# Placa_processamento_modelo_A.net
KiCad netlist of a schematic drawn in EAGLE
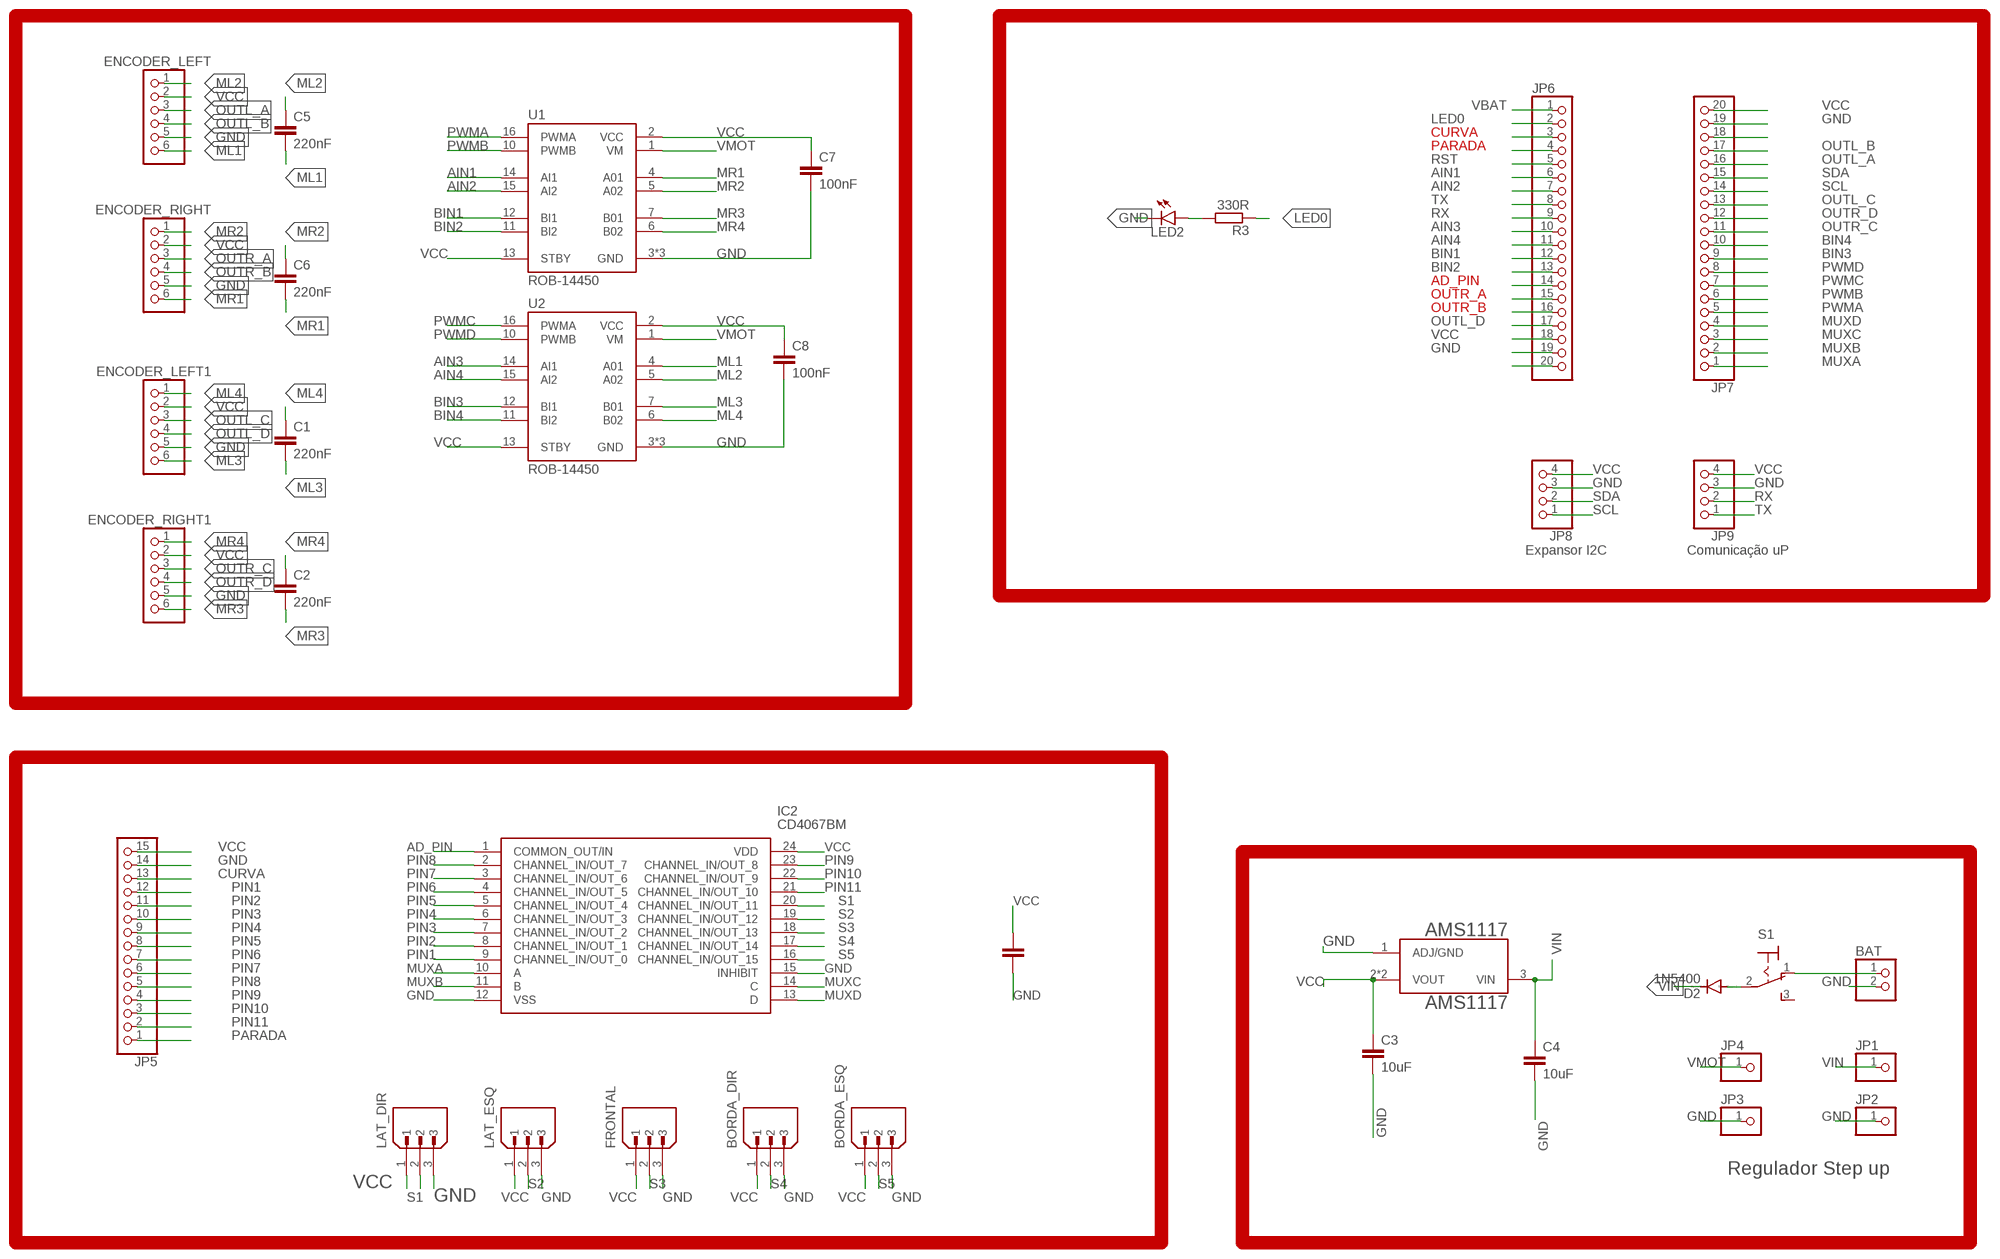
[diagram p0: schematic, sheet 1]

(export (version "E")
  (design (tool "Eeschema 10.0.6"))
  (components
    (comp (ref "AMS1117")
      (value "AMS1117")
      (footprint "eagle-import:SOT229P700X180-4N")
      (fields (field (name "MF") "Advanced Monolithic Systems"))
      (libsource (lib "eagle-import") (part "AMS1117"))
    )
    (comp (ref "BAT")
      (value "PINHD-1X2")
      (footprint "eagle-import:1X02")
      (libsource (lib "eagle-import") (part "PINHD-1X2"))
    )
    (comp (ref "BORDA_DIR")
      (value "B3B-XH-A(LF)(SN)")
      (footprint "eagle-import:JST_B3B-XH-A(LF)(SN)")
      (fields (field (name "MF") "JST Sales"))
      (libsource (lib "eagle-import") (part "B3B-XH-A(LF)(SN)"))
    )
    (comp (ref "BORDA_ESQ")
      (value "B3B-XH-A(LF)(SN)")
      (footprint "eagle-import:JST_B3B-XH-A(LF)(SN)")
      (fields (field (name "MF") "JST Sales"))
      (libsource (lib "eagle-import") (part "B3B-XH-A(LF)(SN)"))
    )
    (comp (ref "C1")
      (value "220nF")
      (footprint "eagle-import:C0805")
      (libsource (lib "eagle-import") (part "C-EUC0805"))
    )
    (comp (ref "C2")
      (value "220nF")
      (footprint "eagle-import:C0805")
      (libsource (lib "eagle-import") (part "C-EUC0805"))
    )
    (comp (ref "C3")
      (value "10uF")
      (footprint "eagle-import:C0805")
      (libsource (lib "eagle-import") (part "C-EUC0805"))
    )
    (comp (ref "C4")
      (value "10uF")
      (footprint "eagle-import:C0805")
      (libsource (lib "eagle-import") (part "C-EUC0805"))
    )
    (comp (ref "C5")
      (value "220nF")
      (footprint "eagle-import:C0805")
      (libsource (lib "eagle-import") (part "C-EUC0805"))
    )
    (comp (ref "C6")
      (value "220nF")
      (footprint "eagle-import:C0805")
      (libsource (lib "eagle-import") (part "C-EUC0805"))
    )
    (comp (ref "C7")
      (value "100nF")
      (footprint "eagle-import:C0805")
      (libsource (lib "eagle-import") (part "C-EUC0805"))
    )
    (comp (ref "C8")
      (value "100nF")
      (footprint "eagle-import:C0805")
      (libsource (lib "eagle-import") (part "C-EUC0805"))
    )
    (comp (ref "C10")
      (value "100nF")
      (footprint "eagle-import:C0805")
      (libsource (lib "eagle-import") (part "C-EUC0805"))
    )
    (comp (ref "D2")
      (value "1N5400")
      (footprint "eagle-import:DO201-15")
      (libsource (lib "eagle-import") (part "1N5400"))
    )
    (comp (ref "ENCODER_LEFT")
      (value "PINHD-1X6")
      (footprint "eagle-import:1X06")
      (libsource (lib "eagle-import") (part "PINHD-1X6"))
    )
    (comp (ref "ENCODER_LEFT1")
      (value "PINHD-1X6")
      (footprint "eagle-import:1X06")
      (libsource (lib "eagle-import") (part "PINHD-1X6"))
    )
    (comp (ref "ENCODER_RIGHT")
      (value "PINHD-1X6")
      (footprint "eagle-import:1X06")
      (libsource (lib "eagle-import") (part "PINHD-1X6"))
    )
    (comp (ref "ENCODER_RIGHT1")
      (value "PINHD-1X6")
      (footprint "eagle-import:1X06")
      (libsource (lib "eagle-import") (part "PINHD-1X6"))
    )
    (comp (ref "FRONTAL")
      (value "B3B-XH-A(LF)(SN)")
      (footprint "eagle-import:JST_B3B-XH-A(LF)(SN)")
      (fields (field (name "MF") "JST Sales"))
      (libsource (lib "eagle-import") (part "B3B-XH-A(LF)(SN)"))
    )
    (comp (ref "IC2")
      (value "CD4067BM")
      (footprint "eagle-import:SOIC127P1030X265-24N")
      (fields (field (name "MOUSER_PART_NUMBER") "595-CD4067BM"))
      (libsource (lib "eagle-import") (part "CD4067BM"))
    )
    (comp (ref "JP1")
      (value "PINHD-1X1")
      (footprint "eagle-import:1X01")
      (libsource (lib "eagle-import") (part "PINHD-1X1"))
    )
    (comp (ref "JP2")
      (value "PINHD-1X1")
      (footprint "eagle-import:1X01")
      (libsource (lib "eagle-import") (part "PINHD-1X1"))
    )
    (comp (ref "JP3")
      (value "PINHD-1X1")
      (footprint "eagle-import:1X01")
      (libsource (lib "eagle-import") (part "PINHD-1X1"))
    )
    (comp (ref "JP4")
      (value "PINHD-1X1")
      (footprint "eagle-import:1X01")
      (libsource (lib "eagle-import") (part "PINHD-1X1"))
    )
    (comp (ref "JP5")
      (value "PINHD-1X15")
      (footprint "eagle-import:1X15")
      (libsource (lib "eagle-import") (part "PINHD-1X15"))
    )
    (comp (ref "JP6")
      (value "PINHD-1X20")
      (footprint "eagle-import:1X20")
      (libsource (lib "eagle-import") (part "PINHD-1X20"))
    )
    (comp (ref "JP7")
      (value "PINHD-1X20")
      (footprint "eagle-import:1X20")
      (libsource (lib "eagle-import") (part "PINHD-1X20"))
    )
    (comp (ref "JP8")
      (value "PINHD-1X4")
      (footprint "eagle-import:1X04")
      (libsource (lib "eagle-import") (part "PINHD-1X4"))
    )
    (comp (ref "JP9")
      (value "PINHD-1X4")
      (footprint "eagle-import:1X04")
      (libsource (lib "eagle-import") (part "PINHD-1X4"))
    )
    (comp (ref "LAT_DIR")
      (value "B3B-XH-A(LF)(SN)")
      (footprint "eagle-import:JST_B3B-XH-A(LF)(SN)")
      (fields (field (name "MF") "JST Sales"))
      (libsource (lib "eagle-import") (part "B3B-XH-A(LF)(SN)"))
    )
    (comp (ref "LAT_ESQ")
      (value "B3B-XH-A(LF)(SN)")
      (footprint "eagle-import:JST_B3B-XH-A(LF)(SN)")
      (fields (field (name "MF") "JST Sales"))
      (libsource (lib "eagle-import") (part "B3B-XH-A(LF)(SN)"))
    )
    (comp (ref "LED2")
      (value "LEDCHIPLED_0805")
      (footprint "eagle-import:CHIPLED_0805")
      (libsource (lib "eagle-import") (part "LEDCHIPLED_0805"))
    )
    (comp (ref "R3")
      (value "330R")
      (footprint "eagle-import:R0805")
      (libsource (lib "eagle-import") (part "R-EU_R0805"))
    )
    (comp (ref "S1")
      (value "320-916")
      (footprint "eagle-import:320-916")
      (libsource (lib "eagle-import") (part "320-916"))
    )
    (comp (ref "U1")
      (value "ROB-14450")
      (footprint "eagle-import:MODULE_ROB-14450")
      (fields (field (name "MF") "SparkFun Electronics"))
      (libsource (lib "eagle-import") (part "ROB-14450"))
    )
    (comp (ref "U2")
      (value "ROB-14450")
      (footprint "eagle-import:MODULE_ROB-14450")
      (fields (field (name "MF") "SparkFun Electronics"))
      (libsource (lib "eagle-import") (part "ROB-14450"))
    )
  )
  (nets
    (net (code "1") (name "/AD_PIN") (class "Default")
      (node (ref "IC2") (pin "1") (pinfunction "COMMON_OUT/IN_1") (pintype "bidirectional"))
      (node (ref "JP6") (pin "14") (pinfunction "14_14") (pintype "passive"))
    )
    (net (code "2") (name "/AIN1") (class "Default")
      (node (ref "JP6") (pin "6") (pinfunction "6_6") (pintype "passive"))
      (node (ref "U1") (pin "14") (pinfunction "AI1_14") (pintype "input"))
    )
    (net (code "3") (name "/AIN2") (class "Default")
      (node (ref "JP6") (pin "7") (pinfunction "7_7") (pintype "passive"))
      (node (ref "U1") (pin "15") (pinfunction "AI2_15") (pintype "input"))
    )
    (net (code "4") (name "/AIN3") (class "Default")
      (node (ref "JP6") (pin "10") (pinfunction "10_10") (pintype "passive"))
      (node (ref "U2") (pin "14") (pinfunction "AI1_14") (pintype "input"))
    )
    (net (code "5") (name "/AIN4") (class "Default")
      (node (ref "JP6") (pin "11") (pinfunction "11_11") (pintype "passive"))
      (node (ref "U2") (pin "15") (pinfunction "AI2_15") (pintype "input"))
    )
    (net (code "6") (name "/BIN1") (class "Default")
      (node (ref "JP6") (pin "12") (pinfunction "12_12") (pintype "passive"))
      (node (ref "U1") (pin "12") (pinfunction "BI1_12") (pintype "input"))
    )
    (net (code "7") (name "/BIN2") (class "Default")
      (node (ref "JP6") (pin "13") (pinfunction "13_13") (pintype "passive"))
      (node (ref "U1") (pin "11") (pinfunction "BI2_11") (pintype "input"))
    )
    (net (code "8") (name "/BIN3") (class "Default")
      (node (ref "JP7") (pin "9") (pinfunction "9_9") (pintype "passive"))
      (node (ref "U2") (pin "12") (pinfunction "BI1_12") (pintype "input"))
    )
    (net (code "9") (name "/BIN4") (class "Default")
      (node (ref "JP7") (pin "10") (pinfunction "10_10") (pintype "passive"))
      (node (ref "U2") (pin "11") (pinfunction "BI2_11") (pintype "input"))
    )
    (net (code "10") (name "/CURVA") (class "Default")
      (node (ref "JP5") (pin "13") (pinfunction "13_13") (pintype "passive"))
      (node (ref "JP6") (pin "3") (pinfunction "3_3") (pintype "passive"))
    )
    (net (code "11") (name "/MUXA") (class "Default")
      (node (ref "IC2") (pin "10") (pinfunction "A_10") (pintype "bidirectional"))
      (node (ref "JP7") (pin "1") (pinfunction "1_1") (pintype "passive"))
    )
    (net (code "12") (name "/MUXB") (class "Default")
      (node (ref "IC2") (pin "11") (pinfunction "B_11") (pintype "bidirectional"))
      (node (ref "JP7") (pin "2") (pinfunction "2_2") (pintype "passive"))
    )
    (net (code "13") (name "/MUXC") (class "Default")
      (node (ref "IC2") (pin "14") (pinfunction "C_14") (pintype "bidirectional"))
      (node (ref "JP7") (pin "3") (pinfunction "3_3") (pintype "passive"))
    )
    (net (code "14") (name "/MUXD") (class "Default")
      (node (ref "IC2") (pin "13") (pinfunction "D_13") (pintype "bidirectional"))
      (node (ref "JP7") (pin "4") (pinfunction "4_4") (pintype "passive"))
    )
    (net (code "15") (name "/PARADA") (class "Default")
      (node (ref "JP5") (pin "1") (pinfunction "1_1") (pintype "passive"))
      (node (ref "JP6") (pin "4") (pinfunction "4_4") (pintype "passive"))
    )
    (net (code "16") (name "/PIN1") (class "Default")
      (node (ref "IC2") (pin "9") (pinfunction "CHANNEL_IN/OUT_0_9") (pintype "bidirectional"))
      (node (ref "JP5") (pin "12") (pinfunction "12_12") (pintype "passive"))
    )
    (net (code "17") (name "/PIN2") (class "Default")
      (node (ref "IC2") (pin "8") (pinfunction "CHANNEL_IN/OUT_1_8") (pintype "bidirectional"))
      (node (ref "JP5") (pin "11") (pinfunction "11_11") (pintype "passive"))
    )
    (net (code "18") (name "/PIN3") (class "Default")
      (node (ref "IC2") (pin "7") (pinfunction "CHANNEL_IN/OUT_2_7") (pintype "bidirectional"))
      (node (ref "JP5") (pin "10") (pinfunction "10_10") (pintype "passive"))
    )
    (net (code "19") (name "/PIN4") (class "Default")
      (node (ref "IC2") (pin "6") (pinfunction "CHANNEL_IN/OUT_3_6") (pintype "bidirectional"))
      (node (ref "JP5") (pin "9") (pinfunction "9_9") (pintype "passive"))
    )
    (net (code "20") (name "/PIN5") (class "Default")
      (node (ref "IC2") (pin "5") (pinfunction "CHANNEL_IN/OUT_4_5") (pintype "bidirectional"))
      (node (ref "JP5") (pin "8") (pinfunction "8_8") (pintype "passive"))
    )
    (net (code "21") (name "/PIN6") (class "Default")
      (node (ref "IC2") (pin "4") (pinfunction "CHANNEL_IN/OUT_5_4") (pintype "bidirectional"))
      (node (ref "JP5") (pin "7") (pinfunction "7_7") (pintype "passive"))
    )
    (net (code "22") (name "/PIN7") (class "Default")
      (node (ref "IC2") (pin "3") (pinfunction "CHANNEL_IN/OUT_6_3") (pintype "bidirectional"))
      (node (ref "JP5") (pin "6") (pinfunction "6_6") (pintype "passive"))
    )
    (net (code "23") (name "/PIN8") (class "Default")
      (node (ref "IC2") (pin "2") (pinfunction "CHANNEL_IN/OUT_7_2") (pintype "bidirectional"))
      (node (ref "JP5") (pin "5") (pinfunction "5_5") (pintype "passive"))
    )
    (net (code "24") (name "/PIN9") (class "Default")
      (node (ref "IC2") (pin "23") (pinfunction "CHANNEL_IN/OUT_8_23") (pintype "bidirectional"))
      (node (ref "JP5") (pin "4") (pinfunction "4_4") (pintype "passive"))
    )
    (net (code "25") (name "/PIN10") (class "Default")
      (node (ref "IC2") (pin "22") (pinfunction "CHANNEL_IN/OUT_9_22") (pintype "bidirectional"))
      (node (ref "JP5") (pin "3") (pinfunction "3_3") (pintype "passive"))
    )
    (net (code "26") (name "/PIN11") (class "Default")
      (node (ref "IC2") (pin "21") (pinfunction "CHANNEL_IN/OUT_10_21") (pintype "bidirectional"))
      (node (ref "JP5") (pin "2") (pinfunction "2_2") (pintype "passive"))
    )
    (net (code "27") (name "/PWMA") (class "Default")
      (node (ref "JP7") (pin "5") (pinfunction "5_5") (pintype "passive"))
      (node (ref "U1") (pin "16") (pinfunction "PWMA_16") (pintype "input"))
    )
    (net (code "28") (name "/PWMB") (class "Default")
      (node (ref "JP7") (pin "6") (pinfunction "6_6") (pintype "passive"))
      (node (ref "U1") (pin "10") (pinfunction "PWMB_10") (pintype "input"))
    )
    (net (code "29") (name "/PWMC") (class "Default")
      (node (ref "JP7") (pin "7") (pinfunction "7_7") (pintype "passive"))
      (node (ref "U2") (pin "16") (pinfunction "PWMA_16") (pintype "input"))
    )
    (net (code "30") (name "/PWMD") (class "Default")
      (node (ref "JP7") (pin "8") (pinfunction "8_8") (pintype "passive"))
      (node (ref "U2") (pin "10") (pinfunction "PWMB_10") (pintype "input"))
    )
    (net (code "31") (name "/RST") (class "Default")
      (node (ref "JP6") (pin "5") (pinfunction "5_5") (pintype "passive"))
    )
    (net (code "32") (name "/RX") (class "Default")
      (node (ref "JP6") (pin "9") (pinfunction "9_9") (pintype "passive"))
      (node (ref "JP9") (pin "2") (pinfunction "2_2") (pintype "passive"))
    )
    (net (code "33") (name "/S1") (class "Default")
      (node (ref "IC2") (pin "20") (pinfunction "CHANNEL_IN/OUT_11_20") (pintype "bidirectional"))
      (node (ref "LAT_DIR") (pin "2") (pinfunction "2_2") (pintype "passive"))
    )
    (net (code "34") (name "/S2") (class "Default")
      (node (ref "IC2") (pin "19") (pinfunction "CHANNEL_IN/OUT_12_19") (pintype "bidirectional"))
      (node (ref "LAT_ESQ") (pin "2") (pinfunction "2_2") (pintype "passive"))
    )
    (net (code "35") (name "/S3") (class "Default")
      (node (ref "FRONTAL") (pin "2") (pinfunction "2_2") (pintype "passive"))
      (node (ref "IC2") (pin "18") (pinfunction "CHANNEL_IN/OUT_13_18") (pintype "bidirectional"))
    )
    (net (code "36") (name "/S4") (class "Default")
      (node (ref "BORDA_DIR") (pin "2") (pinfunction "2_2") (pintype "passive"))
      (node (ref "IC2") (pin "17") (pinfunction "CHANNEL_IN/OUT_14_17") (pintype "bidirectional"))
    )
    (net (code "37") (name "/S5") (class "Default")
      (node (ref "BORDA_ESQ") (pin "2") (pinfunction "2_2") (pintype "passive"))
      (node (ref "IC2") (pin "16") (pinfunction "CHANNEL_IN/OUT_15_16") (pintype "bidirectional"))
    )
    (net (code "38") (name "/SCL") (class "Default")
      (node (ref "JP7") (pin "14") (pinfunction "14_14") (pintype "passive"))
      (node (ref "JP8") (pin "1") (pinfunction "1_1") (pintype "passive"))
    )
    (net (code "39") (name "/SDA") (class "Default")
      (node (ref "JP7") (pin "15") (pinfunction "15_15") (pintype "passive"))
      (node (ref "JP8") (pin "2") (pinfunction "2_2") (pintype "passive"))
    )
    (net (code "40") (name "/TX") (class "Default")
      (node (ref "JP6") (pin "8") (pinfunction "8_8") (pintype "passive"))
      (node (ref "JP9") (pin "1") (pinfunction "1_1") (pintype "passive"))
    )
    (net (code "41") (name "/VBAT") (class "Default")
      (node (ref "JP6") (pin "1") (pinfunction "1_1") (pintype "passive"))
    )
    (net (code "42") (name "/VMOT") (class "Default")
      (node (ref "JP4") (pin "1") (pinfunction "1_1") (pintype "passive"))
      (node (ref "U1") (pin "1") (pinfunction "VM_1") (pintype "power_in"))
      (node (ref "U2") (pin "1") (pinfunction "VM_1") (pintype "power_in"))
    )
    (net (code "43") (name "GND") (class "Default")
      (node (ref "AMS1117") (pin "1") (pinfunction "ADJ/GND_1") (pintype "power_in"))
      (node (ref "BAT") (pin "2") (pinfunction "2_2") (pintype "passive"))
      (node (ref "BORDA_DIR") (pin "3") (pinfunction "3_3") (pintype "passive"))
      (node (ref "BORDA_ESQ") (pin "3") (pinfunction "3_3") (pintype "passive"))
      (node (ref "C10") (pin "2") (pinfunction "2_2") (pintype "passive"))
      (node (ref "C3") (pin "2") (pinfunction "2_2") (pintype "passive"))
      (node (ref "C4") (pin "2") (pinfunction "2_2") (pintype "passive"))
      (node (ref "C7") (pin "2") (pinfunction "2_2") (pintype "passive"))
      (node (ref "C8") (pin "2") (pinfunction "2_2") (pintype "passive"))
      (node (ref "ENCODER_LEFT") (pin "5") (pinfunction "5_5") (pintype "passive"))
      (node (ref "ENCODER_LEFT1") (pin "5") (pinfunction "5_5") (pintype "passive"))
      (node (ref "ENCODER_RIGHT") (pin "5") (pinfunction "5_5") (pintype "passive"))
      (node (ref "ENCODER_RIGHT1") (pin "5") (pinfunction "5_5") (pintype "passive"))
      (node (ref "FRONTAL") (pin "3") (pinfunction "3_3") (pintype "passive"))
      (node (ref "IC2") (pin "12") (pinfunction "VSS_12") (pintype "bidirectional"))
      (node (ref "IC2") (pin "15") (pinfunction "INHIBIT_15") (pintype "bidirectional"))
      (node (ref "JP2") (pin "1") (pinfunction "1_1") (pintype "passive"))
      (node (ref "JP3") (pin "1") (pinfunction "1_1") (pintype "passive"))
      (node (ref "JP5") (pin "14") (pinfunction "14_14") (pintype "passive"))
      (node (ref "JP6") (pin "19") (pinfunction "19_19") (pintype "passive"))
      (node (ref "JP7") (pin "19") (pinfunction "19_19") (pintype "passive"))
      (node (ref "JP8") (pin "3") (pinfunction "3_3") (pintype "passive"))
      (node (ref "JP9") (pin "3") (pinfunction "3_3") (pintype "passive"))
      (node (ref "LAT_DIR") (pin "3") (pinfunction "3_3") (pintype "passive"))
      (node (ref "LAT_ESQ") (pin "3") (pinfunction "3_3") (pintype "passive"))
      (node (ref "LED2") (pin "C") (pinfunction "C_C") (pintype "passive"))
      (node (ref "U1") (pin "3") (pinfunction "GND_3") (pintype "power_in"))
      (node (ref "U1") (pin "8") (pinfunction "GND_8") (pintype "power_in"))
      (node (ref "U1") (pin "9") (pinfunction "GND_9") (pintype "power_in"))
      (node (ref "U2") (pin "3") (pinfunction "GND_3") (pintype "power_in"))
      (node (ref "U2") (pin "8") (pinfunction "GND_8") (pintype "power_in"))
      (node (ref "U2") (pin "9") (pinfunction "GND_9") (pintype "power_in"))
    )
    (net (code "44") (name "LED0") (class "Default")
      (node (ref "JP6") (pin "2") (pinfunction "2_2") (pintype "passive"))
      (node (ref "R3") (pin "1") (pinfunction "1_1") (pintype "passive"))
    )
    (net (code "45") (name "ML1") (class "Default")
      (node (ref "C5") (pin "2") (pinfunction "2_2") (pintype "passive"))
      (node (ref "ENCODER_LEFT") (pin "6") (pinfunction "6_6") (pintype "passive"))
      (node (ref "U2") (pin "4") (pinfunction "A01_4") (pintype "output"))
    )
    (net (code "46") (name "ML2") (class "Default")
      (node (ref "C5") (pin "1") (pinfunction "1_1") (pintype "passive"))
      (node (ref "ENCODER_LEFT") (pin "1") (pinfunction "1_1") (pintype "passive"))
      (node (ref "U2") (pin "5") (pinfunction "A02_5") (pintype "output"))
    )
    (net (code "47") (name "ML3") (class "Default")
      (node (ref "C1") (pin "2") (pinfunction "2_2") (pintype "passive"))
      (node (ref "ENCODER_LEFT1") (pin "6") (pinfunction "6_6") (pintype "passive"))
      (node (ref "U2") (pin "7") (pinfunction "B01_7") (pintype "output"))
    )
    (net (code "48") (name "ML4") (class "Default")
      (node (ref "C1") (pin "1") (pinfunction "1_1") (pintype "passive"))
      (node (ref "ENCODER_LEFT1") (pin "1") (pinfunction "1_1") (pintype "passive"))
      (node (ref "U2") (pin "6") (pinfunction "B02_6") (pintype "output"))
    )
    (net (code "49") (name "MR1") (class "Default")
      (node (ref "C6") (pin "2") (pinfunction "2_2") (pintype "passive"))
      (node (ref "ENCODER_RIGHT") (pin "6") (pinfunction "6_6") (pintype "passive"))
      (node (ref "U1") (pin "4") (pinfunction "A01_4") (pintype "output"))
    )
    (net (code "50") (name "MR2") (class "Default")
      (node (ref "C6") (pin "1") (pinfunction "1_1") (pintype "passive"))
      (node (ref "ENCODER_RIGHT") (pin "1") (pinfunction "1_1") (pintype "passive"))
      (node (ref "U1") (pin "5") (pinfunction "A02_5") (pintype "output"))
    )
    (net (code "51") (name "MR3") (class "Default")
      (node (ref "C2") (pin "2") (pinfunction "2_2") (pintype "passive"))
      (node (ref "ENCODER_RIGHT1") (pin "6") (pinfunction "6_6") (pintype "passive"))
      (node (ref "U1") (pin "7") (pinfunction "B01_7") (pintype "output"))
    )
    (net (code "52") (name "MR4") (class "Default")
      (node (ref "C2") (pin "1") (pinfunction "1_1") (pintype "passive"))
      (node (ref "ENCODER_RIGHT1") (pin "1") (pinfunction "1_1") (pintype "passive"))
      (node (ref "U1") (pin "6") (pinfunction "B02_6") (pintype "output"))
    )
    (net (code "53") (name "Net-(LED2-PadA)") (class "Default")
      (node (ref "LED2") (pin "A") (pinfunction "A_A") (pintype "passive"))
      (node (ref "R3") (pin "2") (pinfunction "2_2") (pintype "passive"))
    )
    (net (code "54") (name "Net-(S1-O)") (class "Default")
      (node (ref "BAT") (pin "1") (pinfunction "1_1") (pintype "passive"))
      (node (ref "S1") (pin "1") (pinfunction "O_1") (pintype "passive"))
    )
    (net (code "55") (name "Net-(S1-P)") (class "Default")
      (node (ref "D2") (pin "A") (pinfunction "A_A") (pintype "passive"))
      (node (ref "S1") (pin "2") (pinfunction "P_2") (pintype "passive"))
    )
    (net (code "56") (name "OUTL_A") (class "Default")
      (node (ref "ENCODER_LEFT") (pin "3") (pinfunction "3_3") (pintype "passive"))
      (node (ref "JP7") (pin "16") (pinfunction "16_16") (pintype "passive"))
    )
    (net (code "57") (name "OUTL_B") (class "Default")
      (node (ref "ENCODER_LEFT") (pin "4") (pinfunction "4_4") (pintype "passive"))
      (node (ref "JP7") (pin "17") (pinfunction "17_17") (pintype "passive"))
    )
    (net (code "58") (name "OUTL_C") (class "Default")
      (node (ref "ENCODER_LEFT1") (pin "3") (pinfunction "3_3") (pintype "passive"))
      (node (ref "JP7") (pin "13") (pinfunction "13_13") (pintype "passive"))
    )
    (net (code "59") (name "OUTL_D") (class "Default")
      (node (ref "ENCODER_LEFT1") (pin "4") (pinfunction "4_4") (pintype "passive"))
      (node (ref "JP6") (pin "17") (pinfunction "17_17") (pintype "passive"))
    )
    (net (code "60") (name "OUTR_A") (class "Default")
      (node (ref "ENCODER_RIGHT") (pin "3") (pinfunction "3_3") (pintype "passive"))
      (node (ref "JP6") (pin "15") (pinfunction "15_15") (pintype "passive"))
    )
    (net (code "61") (name "OUTR_B") (class "Default")
      (node (ref "ENCODER_RIGHT") (pin "4") (pinfunction "4_4") (pintype "passive"))
      (node (ref "JP6") (pin "16") (pinfunction "16_16") (pintype "passive"))
    )
    (net (code "62") (name "OUTR_C") (class "Default")
      (node (ref "ENCODER_RIGHT1") (pin "3") (pinfunction "3_3") (pintype "passive"))
      (node (ref "JP7") (pin "11") (pinfunction "11_11") (pintype "passive"))
    )
    (net (code "63") (name "OUTR_D") (class "Default")
      (node (ref "ENCODER_RIGHT1") (pin "4") (pinfunction "4_4") (pintype "passive"))
      (node (ref "JP7") (pin "12") (pinfunction "12_12") (pintype "passive"))
    )
    (net (code "64") (name "VCC") (class "Default")
      (node (ref "AMS1117") (pin "2") (pinfunction "VOUT_2") (pintype "output"))
      (node (ref "AMS1117") (pin "4") (pinfunction "VOUT_4") (pintype "output"))
      (node (ref "BORDA_DIR") (pin "1") (pinfunction "1_1") (pintype "passive"))
      (node (ref "BORDA_ESQ") (pin "1") (pinfunction "1_1") (pintype "passive"))
      (node (ref "C10") (pin "1") (pinfunction "1_1") (pintype "passive"))
      (node (ref "C3") (pin "1") (pinfunction "1_1") (pintype "passive"))
      (node (ref "C7") (pin "1") (pinfunction "1_1") (pintype "passive"))
      (node (ref "C8") (pin "1") (pinfunction "1_1") (pintype "passive"))
      (node (ref "ENCODER_LEFT") (pin "2") (pinfunction "2_2") (pintype "passive"))
      (node (ref "ENCODER_LEFT1") (pin "2") (pinfunction "2_2") (pintype "passive"))
      (node (ref "ENCODER_RIGHT") (pin "2") (pinfunction "2_2") (pintype "passive"))
      (node (ref "ENCODER_RIGHT1") (pin "2") (pinfunction "2_2") (pintype "passive"))
      (node (ref "FRONTAL") (pin "1") (pinfunction "1_1") (pintype "passive"))
      (node (ref "IC2") (pin "24") (pinfunction "VDD_24") (pintype "bidirectional"))
      (node (ref "JP5") (pin "15") (pinfunction "15_15") (pintype "passive"))
      (node (ref "JP6") (pin "18") (pinfunction "18_18") (pintype "passive"))
      (node (ref "JP7") (pin "20") (pinfunction "20_20") (pintype "passive"))
      (node (ref "JP8") (pin "4") (pinfunction "4_4") (pintype "passive"))
      (node (ref "JP9") (pin "4") (pinfunction "4_4") (pintype "passive"))
      (node (ref "LAT_DIR") (pin "1") (pinfunction "1_1") (pintype "passive"))
      (node (ref "LAT_ESQ") (pin "1") (pinfunction "1_1") (pintype "passive"))
      (node (ref "U1") (pin "13") (pinfunction "STBY_13") (pintype "input"))
      (node (ref "U1") (pin "2") (pinfunction "VCC_2") (pintype "power_in"))
      (node (ref "U2") (pin "13") (pinfunction "STBY_13") (pintype "input"))
      (node (ref "U2") (pin "2") (pinfunction "VCC_2") (pintype "power_in"))
    )
    (net (code "65") (name "VIN") (class "Default")
      (node (ref "AMS1117") (pin "3") (pinfunction "VIN_3") (pintype "input"))
      (node (ref "C4") (pin "1") (pinfunction "1_1") (pintype "passive"))
      (node (ref "D2") (pin "C") (pinfunction "C_C") (pintype "passive"))
      (node (ref "JP1") (pin "1") (pinfunction "1_1") (pintype "passive"))
    )
    (net (code "66") (name "unconnected-(JP6-Pad20)") (class "Default")
      (node (ref "JP6") (pin "20") (pinfunction "20_20") (pintype "passive"))
    )
    (net (code "67") (name "unconnected-(JP7-Pad18)") (class "Default")
      (node (ref "JP7") (pin "18") (pinfunction "18_18") (pintype "passive"))
    )
    (net (code "68") (name "unconnected-(S1-S-Pad3)") (class "Default")
      (node (ref "S1") (pin "3") (pinfunction "S_3") (pintype "passive"))
    )
  )
)
